# working.net
KiCad netlist of a schematic drawn in EAGLE
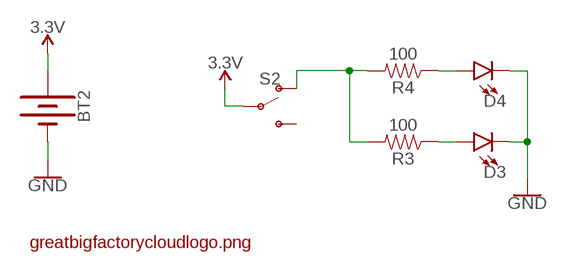
[diagram p0: schematic, sheet 1]

(export (version "E")
  (design (tool "Eeschema 10.0.6"))
  (components
    (comp (ref "BT2")
      (value "BATTERY-20MM_PTH_KIT")
      (footprint "eagle-import:BATTCOM_20MM_PTH_KIT")
      (libsource (lib "eagle-import") (part "BATTERY-20MM_PTH_KIT"))
    )
    (comp (ref "D3")
      (value "LED5MM")
      (footprint "eagle-import:LED_5MM")
      (libsource (lib "eagle-import") (part "LED5MM"))
    )
    (comp (ref "D4")
      (value "LED5MM")
      (footprint "eagle-import:LED_5MM")
      (libsource (lib "eagle-import") (part "LED5MM"))
    )
    (comp (ref "R3")
      (value "100")
      (footprint "eagle-import:AXIAL-0.3EZ")
      (libsource (lib "eagle-import") (part "100OHM-HORIZ_KIT-1/4W-1%"))
    )
    (comp (ref "R4")
      (value "100")
      (footprint "eagle-import:AXIAL-0.3EZ")
      (libsource (lib "eagle-import") (part "100OHM-HORIZ_KIT-1/4W-1%"))
    )
    (comp (ref "S2")
      (value "SWITCH-SPDT-PTH-11.6X4.0MM-KIT")
      (footprint "eagle-import:SWITCH_SPDT_PTH_11.6X4.0MM_KIT")
      (libsource (lib "eagle-import") (part "SWITCH-SPDT-PTH-11.6X4.0MM-KIT"))
    )
    (comp (ref "U$1")
      (value "GREATBIGFACTORYCLOUDLOGO#PNG")
      (footprint "eagle-import:GREATBIGFACTORYCLOUDLOGO#PNG")
      (libsource (lib "eagle-import") (part "GREATBIGFACTORYCLOUDLOGO#PNG"))
    )
  )
  (nets
    (net (code "1") (name "3.3V") (class "Default")
      (node (ref "BT2") (pin "1") (pinfunction "+_1") (pintype "power_in"))
      (node (ref "S2") (pin "2") (pinfunction "P_2") (pintype "passive"))
    )
    (net (code "2") (name "GND") (class "Default")
      (node (ref "BT2") (pin "2") (pinfunction "-_2") (pintype "power_in"))
      (node (ref "D3") (pin "K") (pinfunction "C_K") (pintype "passive"))
      (node (ref "D4") (pin "K") (pinfunction "C_K") (pintype "passive"))
    )
    (net (code "3") (name "Net-(R3-1)") (class "Default")
      (node (ref "D3") (pin "A") (pinfunction "A_A") (pintype "passive"))
      (node (ref "R3") (pin "P$1") (pinfunction "1_P$1") (pintype "passive"))
    )
    (net (code "4") (name "Net-(R3-2)") (class "Default")
      (node (ref "R3") (pin "P$2") (pinfunction "2_P$2") (pintype "passive"))
      (node (ref "R4") (pin "P$2") (pinfunction "2_P$2") (pintype "passive"))
      (node (ref "S2") (pin "1") (pinfunction "O_1") (pintype "passive"))
    )
    (net (code "5") (name "Net-(R4-1)") (class "Default")
      (node (ref "D4") (pin "A") (pinfunction "A_A") (pintype "passive"))
      (node (ref "R4") (pin "P$1") (pinfunction "1_P$1") (pintype "passive"))
    )
    (net (code "6") (name "unconnected-(S2-S-Pad3)") (class "Default")
      (node (ref "S2") (pin "3") (pinfunction "S_3") (pintype "passive"))
    )
  )
)
